# Air_conditioning.net
KiCad netlist of a schematic drawn in Altium Designer
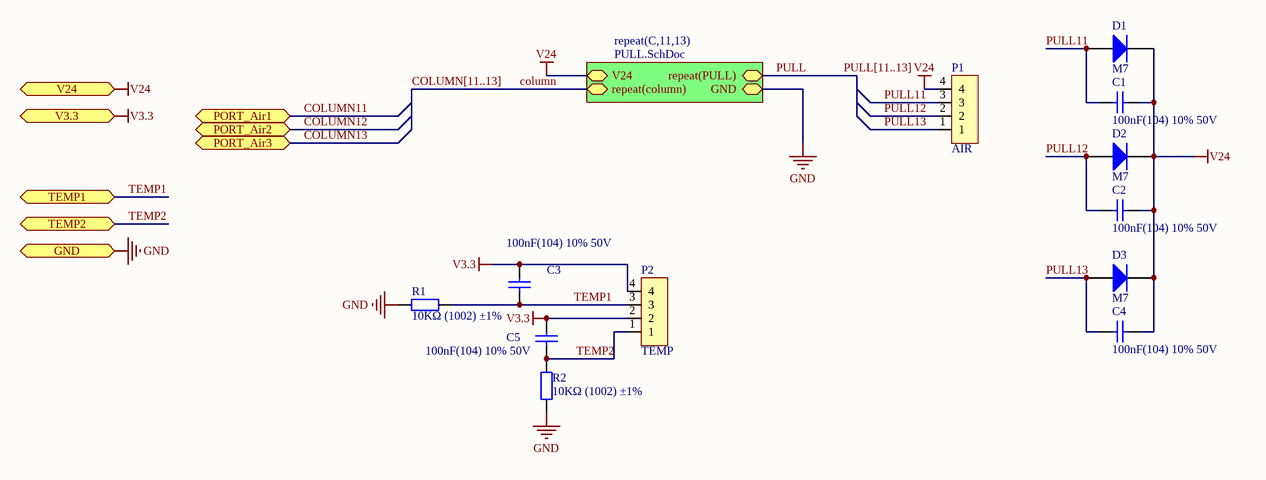
[diagram p0: Air conditioning.SchDoc]

(export (version "E")
  (design (tool "Eeschema 10.0.6"))
  (components
    (comp (ref "C1")
      (value "100nF(104) 10% 50V")
      (footprint "0805_C")
      (description "贴片电容")
      (libsource (lib "Miscellaneous Devices LC") (part "0805 100nF(104) 10% 50V"))
    )
    (comp (ref "C2")
      (value "100nF(104) 10% 50V")
      (footprint "0805_C")
      (description "贴片电容")
      (libsource (lib "Miscellaneous Devices LC") (part "0805 100nF(104) 10% 50V"))
    )
    (comp (ref "C3")
      (value "100nF(104) 10% 50V")
      (footprint "0805_C")
      (description "贴片电容")
      (libsource (lib "Miscellaneous Devices LC") (part "0805 100nF(104) 10% 50V"))
    )
    (comp (ref "C4")
      (value "100nF(104) 10% 50V")
      (footprint "0805_C")
      (description "贴片电容")
      (libsource (lib "Miscellaneous Devices LC") (part "0805 100nF(104) 10% 50V"))
    )
    (comp (ref "C5")
      (value "100nF(104) 10% 50V")
      (footprint "0805_C")
      (description "贴片电容")
      (libsource (lib "Miscellaneous Devices LC") (part "0805 100nF(104) 10% 50V"))
    )
    (comp (ref "D1")
      (value "M7")
      (footprint "SMA(DO-214AC)_S1")
      (description "二极管")
      (libsource (lib "Miscellaneous Devices LC") (part "SMA(DO-214AC) M7"))
    )
    (comp (ref "D2")
      (value "M7")
      (footprint "SMA(DO-214AC)_S1")
      (description "二极管")
      (libsource (lib "Miscellaneous Devices LC") (part "SMA(DO-214AC) M7"))
    )
    (comp (ref "D3")
      (value "M7")
      (footprint "SMA(DO-214AC)_S1")
      (description "二极管")
      (libsource (lib "Miscellaneous Devices LC") (part "SMA(DO-214AC) M7"))
    )
    (comp (ref "P1") (value "AIR") (footprint "4P_XH2.54") (libsource (lib "mylib") (part "4P_XH2.54")))
    (comp (ref "P2") (value "TEMP") (footprint "4P_XH2.54") (libsource (lib "mylib") (part "4P_XH2.54")))
    (comp (ref "R1")
      (value "10KΩ (1002) ±1%")
      (footprint "0805_R")
      (description "贴片电阻")
      (libsource (lib "") (part "0805 10KΩ (1002) 1%_1"))
    )
    (comp (ref "R2")
      (value "10KΩ (1002) ±1%")
      (footprint "0805_R")
      (description "贴片电阻")
      (libsource (lib "Miscellaneous Devices LC") (part "0805 10KΩ (1002) 1%"))
    )
  )
  (nets
    (net (code "6") (name "/PULL11") (class "Default")
      (node (ref "C1") (pin "1") (pinfunction "1_1") (pintype "passive"))
      (node (ref "D1") (pin "1") (pinfunction "A_1") (pintype "passive"))
      (node (ref "P1") (pin "3") (pinfunction "3_3") (pintype "passive"))
    )
    (net (code "7") (name "/PULL12") (class "Default")
      (node (ref "C2") (pin "1") (pinfunction "1_1") (pintype "passive"))
      (node (ref "D2") (pin "1") (pinfunction "A_1") (pintype "passive"))
      (node (ref "P1") (pin "2") (pinfunction "2_2") (pintype "passive"))
    )
    (net (code "8") (name "/PULL13") (class "Default")
      (node (ref "C4") (pin "1") (pinfunction "1_1") (pintype "passive"))
      (node (ref "D3") (pin "1") (pinfunction "A_1") (pintype "passive"))
      (node (ref "P1") (pin "1") (pinfunction "1_1") (pintype "passive"))
    )
    (net (code "10") (name "/TEMP1") (class "Default")
      (node (ref "C3") (pin "2") (pinfunction "2_2") (pintype "passive"))
      (node (ref "P2") (pin "3") (pinfunction "3_3") (pintype "passive"))
      (node (ref "R1") (pin "1") (pinfunction "1_1") (pintype "passive"))
    )
    (net (code "11") (name "/TEMP2") (class "Default")
      (node (ref "C5") (pin "2") (pinfunction "2_2") (pintype "passive"))
      (node (ref "P2") (pin "1") (pinfunction "1_1") (pintype "passive"))
      (node (ref "R2") (pin "1") (pinfunction "1_1") (pintype "passive"))
    )
    (net (code "13") (name "GND") (class "Default")
      (node (ref "R1") (pin "2") (pinfunction "2_2") (pintype "passive"))
      (node (ref "R2") (pin "2") (pinfunction "2_2") (pintype "passive"))
    )
    (net (code "14") (name "V3.3") (class "Default")
      (node (ref "C3") (pin "1") (pinfunction "1_1") (pintype "passive"))
      (node (ref "C5") (pin "1") (pinfunction "1_1") (pintype "passive"))
      (node (ref "P2") (pin "2") (pinfunction "2_2") (pintype "passive"))
      (node (ref "P2") (pin "4") (pinfunction "4_4") (pintype "passive"))
    )
    (net (code "15") (name "V24") (class "Default")
      (node (ref "C1") (pin "2") (pinfunction "2_2") (pintype "passive"))
      (node (ref "C2") (pin "2") (pinfunction "2_2") (pintype "passive"))
      (node (ref "C4") (pin "2") (pinfunction "2_2") (pintype "passive"))
      (node (ref "D1") (pin "2") (pinfunction "K_2") (pintype "passive"))
      (node (ref "D2") (pin "2") (pinfunction "K_2") (pintype "passive"))
      (node (ref "D3") (pin "2") (pinfunction "K_2") (pintype "passive"))
      (node (ref "P1") (pin "4") (pinfunction "4_4") (pintype "passive"))
    )
  )
)
